# PiezoAmpHVDCv3.net
KiCad netlist of a schematic drawn in EAGLE
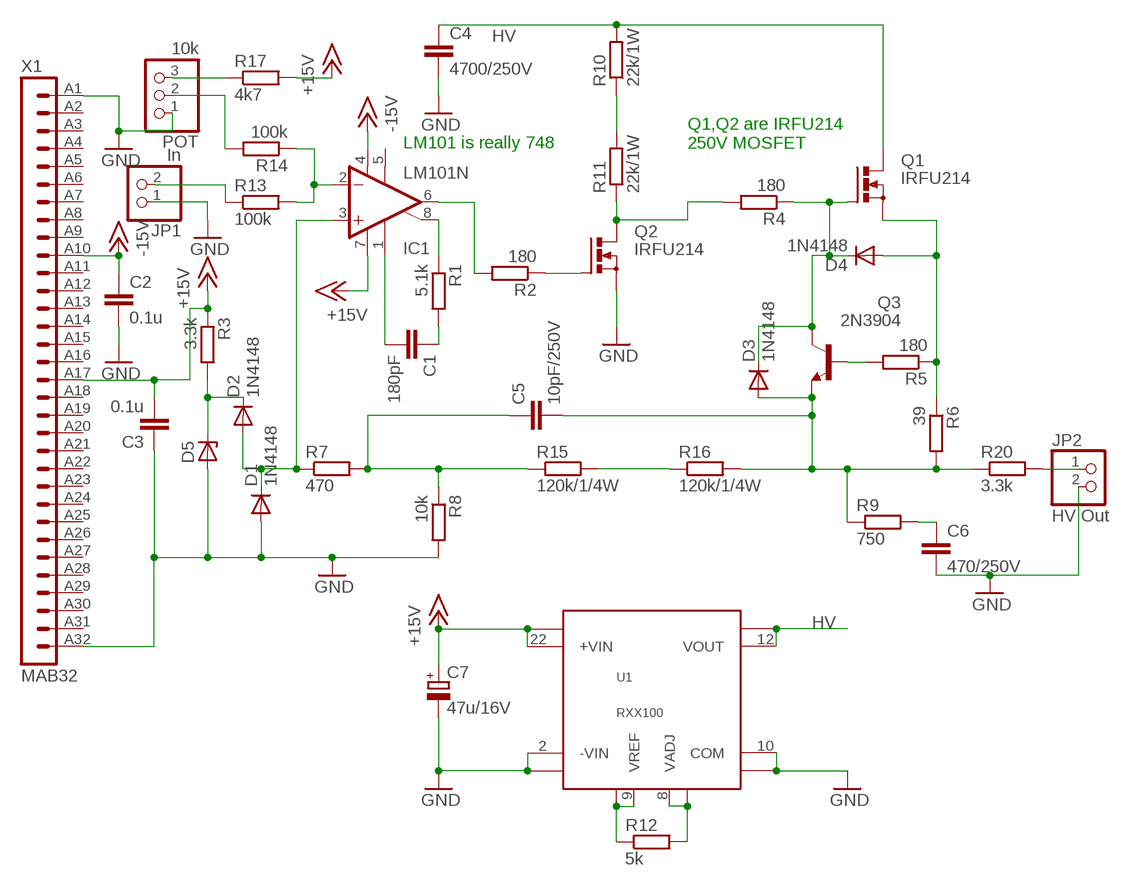
[diagram p0: schematic, sheet 1]

(export (version "E")
  (design (tool "Eeschema 10.0.6"))
  (components
    (comp (ref "C1")
      (value "180pF")
      (footprint "eagle-import:C050-030X075")
      (libsource (lib "eagle-import") (part "C-EU050-030X075"))
    )
    (comp (ref "C2")
      (value "0.1u")
      (footprint "eagle-import:C050-030X075")
      (libsource (lib "eagle-import") (part "C-EU050-030X075"))
    )
    (comp (ref "C3")
      (value "0.1u")
      (footprint "eagle-import:C050-030X075")
      (libsource (lib "eagle-import") (part "C-EU050-030X075"))
    )
    (comp (ref "C4")
      (value "4700/250V")
      (footprint "eagle-import:C075-032X103")
      (libsource (lib "eagle-import") (part "C-EU075-032X103"))
    )
    (comp (ref "C5")
      (value "10pF/250V")
      (footprint "eagle-import:C075-032X103")
      (libsource (lib "eagle-import") (part "C-EU075-032X103"))
    )
    (comp (ref "C6")
      (value "470/250V")
      (footprint "eagle-import:C075-032X103")
      (libsource (lib "eagle-import") (part "C-EU075-032X103"))
    )
    (comp (ref "C7")
      (value "47u/16V")
      (footprint "eagle-import:SANYO-OSCON_F8")
      (libsource (lib "eagle-import") (part "CPOL-EUSANYO_F8"))
    )
    (comp (ref "D1")
      (value "1N4148")
      (footprint "eagle-import:DO35-7")
      (libsource (lib "eagle-import") (part "1N4148DO35-7"))
    )
    (comp (ref "D2")
      (value "1N4148")
      (footprint "eagle-import:DO35-7")
      (libsource (lib "eagle-import") (part "1N4148DO35-7"))
    )
    (comp (ref "D3")
      (value "1N4148")
      (footprint "eagle-import:DO35-7")
      (libsource (lib "eagle-import") (part "1N4148DO35-7"))
    )
    (comp (ref "D4")
      (value "1N4148")
      (footprint "eagle-import:DO35-7")
      (libsource (lib "eagle-import") (part "1N4148DO35-7"))
    )
    (comp (ref "D5")
      (value "ZENER-DIODEDO34-7")
      (footprint "eagle-import:DO34Z7")
      (libsource (lib "eagle-import") (part "ZENER-DIODEDO34-7"))
    )
    (comp (ref "IC1")
      (value "LM101N")
      (footprint "eagle-import:DIL08")
      (libsource (lib "eagle-import") (part "LM101N"))
    )
    (comp (ref "JP1")
      (value "In")
      (footprint "eagle-import:1X02")
      (libsource (lib "eagle-import") (part "PINHD-1X2"))
    )
    (comp (ref "JP2")
      (value "HV Out")
      (footprint "eagle-import:1X02")
      (libsource (lib "eagle-import") (part "PINHD-1X2"))
    )
    (comp (ref "POT")
      (value "10k")
      (footprint "eagle-import:1X03")
      (libsource (lib "eagle-import") (part "PINHD-1X3"))
    )
    (comp (ref "Q1")
      (value "IRFU214")
      (footprint "eagle-import:TO220BV")
      (libsource (lib "eagle-import") (part "IRF512"))
    )
    (comp (ref "Q2")
      (value "IRFU214")
      (footprint "eagle-import:TO220BV")
      (libsource (lib "eagle-import") (part "IRF512"))
    )
    (comp (ref "Q3")
      (value "2N3904")
      (footprint "eagle-import:TO92")
      (libsource (lib "eagle-import") (part "2N3904"))
    )
    (comp (ref "R1")
      (value "5.1k")
      (footprint "eagle-import:0204_7")
      (libsource (lib "eagle-import") (part "R-EU_0204/7"))
    )
    (comp (ref "R2")
      (value "180")
      (footprint "eagle-import:0204_7")
      (libsource (lib "eagle-import") (part "R-EU_0204/7"))
    )
    (comp (ref "R3")
      (value "3.3k")
      (footprint "eagle-import:0204_7")
      (libsource (lib "eagle-import") (part "R-EU_0204/7"))
    )
    (comp (ref "R4")
      (value "180")
      (footprint "eagle-import:0204_7")
      (libsource (lib "eagle-import") (part "R-EU_0204/7"))
    )
    (comp (ref "R5")
      (value "180")
      (footprint "eagle-import:0204_7")
      (libsource (lib "eagle-import") (part "R-EU_0204/7"))
    )
    (comp (ref "R6")
      (value "39")
      (footprint "eagle-import:0204_7")
      (libsource (lib "eagle-import") (part "R-EU_0204/7"))
    )
    (comp (ref "R7")
      (value "470")
      (footprint "eagle-import:0204_7")
      (libsource (lib "eagle-import") (part "R-EU_0204/7"))
    )
    (comp (ref "R8")
      (value "10k")
      (footprint "eagle-import:0204_7")
      (libsource (lib "eagle-import") (part "R-EU_0204/7"))
    )
    (comp (ref "R9")
      (value "750")
      (footprint "eagle-import:0204_7")
      (libsource (lib "eagle-import") (part "R-EU_0204/7"))
    )
    (comp (ref "R10")
      (value "22k/1W")
      (footprint "eagle-import:0411_15")
      (libsource (lib "eagle-import") (part "R-EU_0411/15"))
    )
    (comp (ref "R11")
      (value "22k/1W")
      (footprint "eagle-import:0411_15")
      (libsource (lib "eagle-import") (part "R-EU_0411/15"))
    )
    (comp (ref "R12")
      (value "5k")
      (footprint "eagle-import:0204_7")
      (libsource (lib "eagle-import") (part "R-EU_0204/7"))
    )
    (comp (ref "R13")
      (value "100k")
      (footprint "eagle-import:0204_5")
      (libsource (lib "eagle-import") (part "R-EU_0204/5"))
    )
    (comp (ref "R14")
      (value "100k")
      (footprint "eagle-import:0204_5")
      (libsource (lib "eagle-import") (part "R-EU_0204/5"))
    )
    (comp (ref "R15")
      (value "120k/1/4W")
      (footprint "eagle-import:0411_15")
      (libsource (lib "eagle-import") (part "R-EU_0411/15"))
    )
    (comp (ref "R16")
      (value "120k/1/4W")
      (footprint "eagle-import:0411_15")
      (libsource (lib "eagle-import") (part "R-EU_0411/15"))
    )
    (comp (ref "R17")
      (value "4k7")
      (footprint "eagle-import:0204_5")
      (libsource (lib "eagle-import") (part "R-EU_0204/5"))
    )
    (comp (ref "R20")
      (value "3.3k")
      (footprint "eagle-import:0204_7")
      (libsource (lib "eagle-import") (part "R-EU_0204/7"))
    )
    (comp (ref "U1")
      (value "RXX100")
      (footprint "eagle-import:RXXDIP")
      (libsource (lib "eagle-import") (part "RXX100"))
    )
    (comp (ref "X1")
      (value "MAB32")
      (footprint "eagle-import:MAB32")
      (libsource (lib "eagle-import") (part "MAB32"))
    )
  )
  (nets
    (net (code "1") (name "+15V") (class "Default")
      (node (ref "C3") (pin "2") (pinfunction "2_2") (pintype "passive"))
      (node (ref "C7") (pin "+") (pinfunction "+_+") (pintype "passive"))
      (node (ref "IC1") (pin "7") (pinfunction "V+_7") (pintype "power_in"))
      (node (ref "R17") (pin "2") (pinfunction "2_2") (pintype "passive"))
      (node (ref "R3") (pin "1") (pinfunction "1_1") (pintype "passive"))
      (node (ref "U1") (pin "22") (pinfunction "+VIN_22") (pintype "power_in"))
      (node (ref "U1") (pin "23") (pinfunction "VIN2+_23") (pintype "power_in"))
      (node (ref "X1") (pin "A17") (pinfunction "17_A17") (pintype "passive"))
    )
    (net (code "2") (name "-15V") (class "Default")
      (node (ref "C2") (pin "1") (pinfunction "1_1") (pintype "passive"))
      (node (ref "IC1") (pin "4") (pinfunction "V-_4") (pintype "power_in"))
      (node (ref "X1") (pin "A10") (pinfunction "10_A10") (pintype "passive"))
    )
    (net (code "3") (name "/HV") (class "Default")
      (node (ref "C4") (pin "1") (pinfunction "1_1") (pintype "passive"))
      (node (ref "Q1") (pin "D") (pinfunction "D_D") (pintype "passive"))
      (node (ref "R10") (pin "2") (pinfunction "2_2") (pintype "passive"))
      (node (ref "U1") (pin "12") (pinfunction "VOUT_12") (pintype "power_in"))
      (node (ref "U1") (pin "13") (pinfunction "VOUT2_13") (pintype "power_in"))
    )
    (net (code "4") (name "GND") (class "Default")
      (node (ref "C2") (pin "2") (pinfunction "2_2") (pintype "passive"))
      (node (ref "C3") (pin "1") (pinfunction "1_1") (pintype "passive"))
      (node (ref "C4") (pin "2") (pinfunction "2_2") (pintype "passive"))
      (node (ref "C6") (pin "2") (pinfunction "2_2") (pintype "passive"))
      (node (ref "C7") (pin "-") (pinfunction "-_-") (pintype "passive"))
      (node (ref "D1") (pin "A") (pinfunction "A_A") (pintype "passive"))
      (node (ref "D5") (pin "A") (pinfunction "A_A") (pintype "passive"))
      (node (ref "JP1") (pin "1") (pinfunction "1_1") (pintype "passive"))
      (node (ref "JP2") (pin "2") (pinfunction "2_2") (pintype "passive"))
      (node (ref "POT") (pin "1") (pinfunction "1_1") (pintype "passive"))
      (node (ref "Q2") (pin "S") (pinfunction "S_S") (pintype "passive"))
      (node (ref "R8") (pin "2") (pinfunction "2_2") (pintype "passive"))
      (node (ref "U1") (pin "10") (pinfunction "COM_10") (pintype "power_in"))
      (node (ref "U1") (pin "15") (pinfunction "COM2_15") (pintype "power_in"))
      (node (ref "U1") (pin "2") (pinfunction "-VIN_2") (pintype "power_in"))
      (node (ref "U1") (pin "3") (pinfunction "VIN2-_3") (pintype "power_in"))
      (node (ref "X1") (pin "A1") (pinfunction "1_A1") (pintype "passive"))
      (node (ref "X1") (pin "A32") (pinfunction "32_A32") (pintype "passive"))
    )
    (net (code "5") (name "Net-(C1-Pad1)") (class "Default")
      (node (ref "C1") (pin "1") (pinfunction "1_1") (pintype "passive"))
      (node (ref "R1") (pin "2") (pinfunction "2_2") (pintype "passive"))
    )
    (net (code "6") (name "Net-(C5-Pad1)") (class "Default")
      (node (ref "C5") (pin "1") (pinfunction "1_1") (pintype "passive"))
      (node (ref "R15") (pin "1") (pinfunction "1_1") (pintype "passive"))
      (node (ref "R7") (pin "2") (pinfunction "2_2") (pintype "passive"))
      (node (ref "R8") (pin "1") (pinfunction "1_1") (pintype "passive"))
    )
    (net (code "7") (name "Net-(C6-Pad1)") (class "Default")
      (node (ref "C6") (pin "1") (pinfunction "1_1") (pintype "passive"))
      (node (ref "R9") (pin "2") (pinfunction "2_2") (pintype "passive"))
    )
    (net (code "8") (name "Net-(D2-PadC)") (class "Default")
      (node (ref "D2") (pin "C") (pinfunction "C_C") (pintype "passive"))
      (node (ref "D5") (pin "C") (pinfunction "C_C") (pintype "passive"))
      (node (ref "R3") (pin "2") (pinfunction "2_2") (pintype "passive"))
    )
    (net (code "9") (name "Net-(D4-PadA)") (class "Default")
      (node (ref "D4") (pin "A") (pinfunction "A_A") (pintype "passive"))
      (node (ref "Q1") (pin "S") (pinfunction "S_S") (pintype "passive"))
      (node (ref "R5") (pin "1") (pinfunction "1_1") (pintype "passive"))
      (node (ref "R6") (pin "1") (pinfunction "1_1") (pintype "passive"))
    )
    (net (code "10") (name "Net-(IC1-+IN)") (class "Default")
      (node (ref "D1") (pin "C") (pinfunction "C_C") (pintype "passive"))
      (node (ref "D2") (pin "A") (pinfunction "A_A") (pintype "passive"))
      (node (ref "IC1") (pin "3") (pinfunction "+IN_3") (pintype "input"))
      (node (ref "R7") (pin "1") (pinfunction "1_1") (pintype "passive"))
    )
    (net (code "11") (name "Net-(IC1--IN)") (class "Default")
      (node (ref "IC1") (pin "2") (pinfunction "-IN_2") (pintype "input"))
      (node (ref "R13") (pin "2") (pinfunction "2_2") (pintype "passive"))
      (node (ref "R14") (pin "1") (pinfunction "1_1") (pintype "passive"))
    )
    (net (code "12") (name "Net-(IC1-ON1)") (class "Default")
      (node (ref "C1") (pin "2") (pinfunction "2_2") (pintype "passive"))
      (node (ref "IC1") (pin "1") (pinfunction "ON1_1") (pintype "passive"))
    )
    (net (code "13") (name "Net-(IC1-ON2)") (class "Default")
      (node (ref "IC1") (pin "8") (pinfunction "ON2_8") (pintype "passive"))
      (node (ref "R1") (pin "1") (pinfunction "1_1") (pintype "passive"))
    )
    (net (code "14") (name "Net-(IC1-OUT)") (class "Default")
      (node (ref "IC1") (pin "6") (pinfunction "OUT_6") (pintype "output"))
      (node (ref "R2") (pin "2") (pinfunction "2_2") (pintype "passive"))
    )
    (net (code "15") (name "Net-(JP1-Pad2)") (class "Default")
      (node (ref "JP1") (pin "2") (pinfunction "2_2") (pintype "passive"))
      (node (ref "R13") (pin "1") (pinfunction "1_1") (pintype "passive"))
    )
    (net (code "16") (name "Net-(JP2-Pad1)") (class "Default")
      (node (ref "JP2") (pin "1") (pinfunction "1_1") (pintype "passive"))
      (node (ref "R20") (pin "2") (pinfunction "2_2") (pintype "passive"))
    )
    (net (code "17") (name "Net-(POT-Pad2)") (class "Default")
      (node (ref "POT") (pin "2") (pinfunction "2_2") (pintype "passive"))
      (node (ref "R14") (pin "2") (pinfunction "2_2") (pintype "passive"))
    )
    (net (code "18") (name "Net-(POT-Pad3)") (class "Default")
      (node (ref "POT") (pin "3") (pinfunction "3_3") (pintype "passive"))
      (node (ref "R17") (pin "1") (pinfunction "1_1") (pintype "passive"))
    )
    (net (code "19") (name "Net-(Q2-PadD)") (class "Default")
      (node (ref "Q2") (pin "D") (pinfunction "D_D") (pintype "passive"))
      (node (ref "R11") (pin "1") (pinfunction "1_1") (pintype "passive"))
      (node (ref "R4") (pin "2") (pinfunction "2_2") (pintype "passive"))
    )
    (net (code "20") (name "Net-(Q2-PadG)") (class "Default")
      (node (ref "Q2") (pin "G") (pinfunction "G_G") (pintype "passive"))
      (node (ref "R2") (pin "1") (pinfunction "1_1") (pintype "passive"))
    )
    (net (code "21") (name "Net-(Q3-B)") (class "Default")
      (node (ref "Q3") (pin "2") (pinfunction "B_2") (pintype "passive"))
      (node (ref "R5") (pin "2") (pinfunction "2_2") (pintype "passive"))
    )
    (net (code "22") (name "Net-(Q3-C)") (class "Default")
      (node (ref "D3") (pin "C") (pinfunction "C_C") (pintype "passive"))
      (node (ref "D4") (pin "C") (pinfunction "C_C") (pintype "passive"))
      (node (ref "Q1") (pin "G") (pinfunction "G_G") (pintype "passive"))
      (node (ref "Q3") (pin "1") (pinfunction "C_1") (pintype "passive"))
      (node (ref "R4") (pin "1") (pinfunction "1_1") (pintype "passive"))
    )
    (net (code "23") (name "Net-(Q3-E)") (class "Default")
      (node (ref "C5") (pin "2") (pinfunction "2_2") (pintype "passive"))
      (node (ref "D3") (pin "A") (pinfunction "A_A") (pintype "passive"))
      (node (ref "Q3") (pin "3") (pinfunction "E_3") (pintype "passive"))
      (node (ref "R16") (pin "2") (pinfunction "2_2") (pintype "passive"))
      (node (ref "R20") (pin "1") (pinfunction "1_1") (pintype "passive"))
      (node (ref "R6") (pin "2") (pinfunction "2_2") (pintype "passive"))
      (node (ref "R9") (pin "1") (pinfunction "1_1") (pintype "passive"))
    )
    (net (code "24") (name "Net-(R10-Pad1)") (class "Default")
      (node (ref "R10") (pin "1") (pinfunction "1_1") (pintype "passive"))
      (node (ref "R11") (pin "2") (pinfunction "2_2") (pintype "passive"))
    )
    (net (code "25") (name "Net-(R15-Pad2)") (class "Default")
      (node (ref "R15") (pin "2") (pinfunction "2_2") (pintype "passive"))
      (node (ref "R16") (pin "1") (pinfunction "1_1") (pintype "passive"))
    )
    (net (code "26") (name "Net-(U1-VADJ)") (class "Default")
      (node (ref "R12") (pin "2") (pinfunction "2_2") (pintype "passive"))
      (node (ref "U1") (pin "17") (pinfunction "VADJ2_17") (pintype "input"))
      (node (ref "U1") (pin "8") (pinfunction "VADJ_8") (pintype "input"))
    )
    (net (code "27") (name "Net-(U1-VREF)") (class "Default")
      (node (ref "R12") (pin "1") (pinfunction "1_1") (pintype "passive"))
      (node (ref "U1") (pin "16") (pinfunction "VREF2_16") (pintype "output"))
      (node (ref "U1") (pin "9") (pinfunction "VREF_9") (pintype "output"))
    )
    (net (code "28") (name "unconnected-(IC1-OPT-Pad5)") (class "Default")
      (node (ref "IC1") (pin "5") (pinfunction "OPT_5") (pintype "passive"))
    )
    (net (code "29") (name "unconnected-(X1-2-PadA2)") (class "Default")
      (node (ref "X1") (pin "A2") (pinfunction "2_A2") (pintype "passive"))
    )
    (net (code "30") (name "unconnected-(X1-3-PadA3)") (class "Default")
      (node (ref "X1") (pin "A3") (pinfunction "3_A3") (pintype "passive"))
    )
    (net (code "31") (name "unconnected-(X1-4-PadA4)") (class "Default")
      (node (ref "X1") (pin "A4") (pinfunction "4_A4") (pintype "passive"))
    )
    (net (code "32") (name "unconnected-(X1-5-PadA5)") (class "Default")
      (node (ref "X1") (pin "A5") (pinfunction "5_A5") (pintype "passive"))
    )
    (net (code "33") (name "unconnected-(X1-6-PadA6)") (class "Default")
      (node (ref "X1") (pin "A6") (pinfunction "6_A6") (pintype "passive"))
    )
    (net (code "34") (name "unconnected-(X1-7-PadA7)") (class "Default")
      (node (ref "X1") (pin "A7") (pinfunction "7_A7") (pintype "passive"))
    )
    (net (code "35") (name "unconnected-(X1-8-PadA8)") (class "Default")
      (node (ref "X1") (pin "A8") (pinfunction "8_A8") (pintype "passive"))
    )
    (net (code "36") (name "unconnected-(X1-9-PadA9)") (class "Default")
      (node (ref "X1") (pin "A9") (pinfunction "9_A9") (pintype "passive"))
    )
    (net (code "37") (name "unconnected-(X1-11-PadA11)") (class "Default")
      (node (ref "X1") (pin "A11") (pinfunction "11_A11") (pintype "passive"))
    )
    (net (code "38") (name "unconnected-(X1-12-PadA12)") (class "Default")
      (node (ref "X1") (pin "A12") (pinfunction "12_A12") (pintype "passive"))
    )
    (net (code "39") (name "unconnected-(X1-13-PadA13)") (class "Default")
      (node (ref "X1") (pin "A13") (pinfunction "13_A13") (pintype "passive"))
    )
    (net (code "40") (name "unconnected-(X1-14-PadA14)") (class "Default")
      (node (ref "X1") (pin "A14") (pinfunction "14_A14") (pintype "passive"))
    )
    (net (code "41") (name "unconnected-(X1-15-PadA15)") (class "Default")
      (node (ref "X1") (pin "A15") (pinfunction "15_A15") (pintype "passive"))
    )
    (net (code "42") (name "unconnected-(X1-16-PadA16)") (class "Default")
      (node (ref "X1") (pin "A16") (pinfunction "16_A16") (pintype "passive"))
    )
    (net (code "43") (name "unconnected-(X1-18-PadA18)") (class "Default")
      (node (ref "X1") (pin "A18") (pinfunction "18_A18") (pintype "passive"))
    )
    (net (code "44") (name "unconnected-(X1-19-PadA19)") (class "Default")
      (node (ref "X1") (pin "A19") (pinfunction "19_A19") (pintype "passive"))
    )
    (net (code "45") (name "unconnected-(X1-20-PadA20)") (class "Default")
      (node (ref "X1") (pin "A20") (pinfunction "20_A20") (pintype "passive"))
    )
    (net (code "46") (name "unconnected-(X1-21-PadA21)") (class "Default")
      (node (ref "X1") (pin "A21") (pinfunction "21_A21") (pintype "passive"))
    )
    (net (code "47") (name "unconnected-(X1-22-PadA22)") (class "Default")
      (node (ref "X1") (pin "A22") (pinfunction "22_A22") (pintype "passive"))
    )
    (net (code "48") (name "unconnected-(X1-23-PadA23)") (class "Default")
      (node (ref "X1") (pin "A23") (pinfunction "23_A23") (pintype "passive"))
    )
    (net (code "49") (name "unconnected-(X1-24-PadA24)") (class "Default")
      (node (ref "X1") (pin "A24") (pinfunction "24_A24") (pintype "passive"))
    )
    (net (code "50") (name "unconnected-(X1-25-PadA25)") (class "Default")
      (node (ref "X1") (pin "A25") (pinfunction "25_A25") (pintype "passive"))
    )
    (net (code "51") (name "unconnected-(X1-26-PadA26)") (class "Default")
      (node (ref "X1") (pin "A26") (pinfunction "26_A26") (pintype "passive"))
    )
    (net (code "52") (name "unconnected-(X1-27-PadA27)") (class "Default")
      (node (ref "X1") (pin "A27") (pinfunction "27_A27") (pintype "passive"))
    )
    (net (code "53") (name "unconnected-(X1-28-PadA28)") (class "Default")
      (node (ref "X1") (pin "A28") (pinfunction "28_A28") (pintype "passive"))
    )
    (net (code "54") (name "unconnected-(X1-29-PadA29)") (class "Default")
      (node (ref "X1") (pin "A29") (pinfunction "29_A29") (pintype "passive"))
    )
    (net (code "55") (name "unconnected-(X1-30-PadA30)") (class "Default")
      (node (ref "X1") (pin "A30") (pinfunction "30_A30") (pintype "passive"))
    )
    (net (code "56") (name "unconnected-(X1-31-PadA31)") (class "Default")
      (node (ref "X1") (pin "A31") (pinfunction "31_A31") (pintype "passive"))
    )
  )
)
